# host_connector.net
KiCad netlist of a schematic drawn in Altium Designer
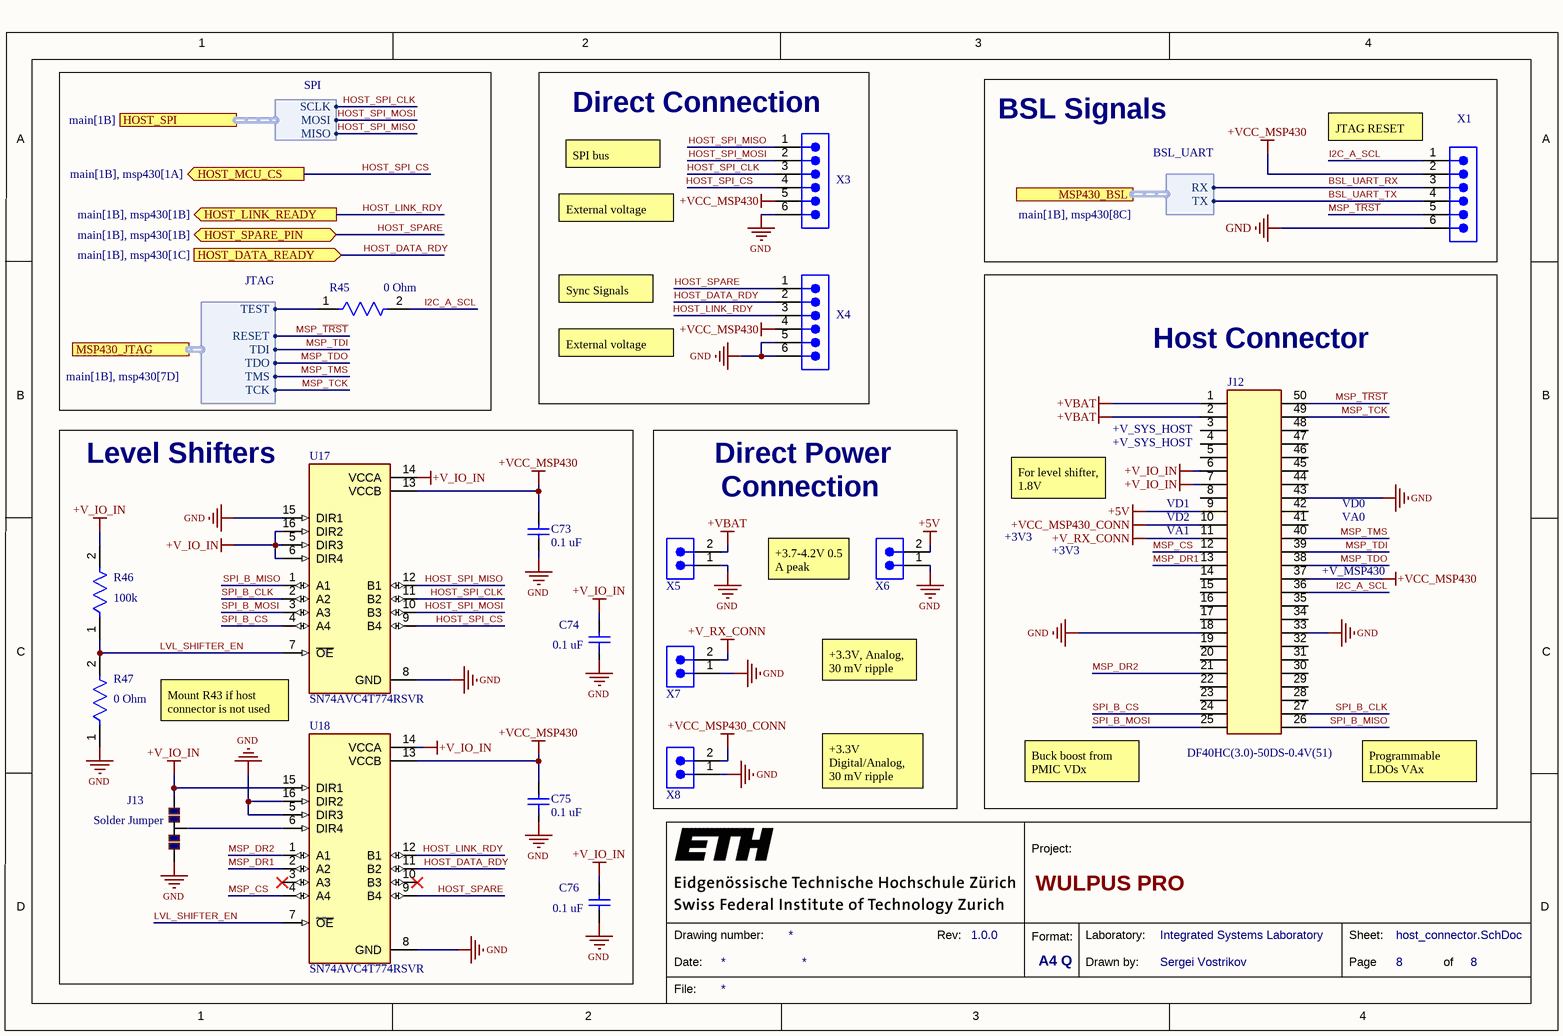
[diagram p0: host_connector.SchDoc]

(export (version "E")
  (design (tool "Eeschema 10.0.6"))
  (components
    (comp (ref "C73")
      (value "0.1 uF")
      (footprint "CAPC1005X55X30LL05T10")
      (description "C0402C104K4RACTU")
      (fields (field (name "MANUFACTURER") "Kemet"))
      (libsource (lib "Altium Content Vault") (part "CAP"))
    )
    (comp (ref "C74")
      (value "0.1 uF")
      (footprint "CAPC1005X55X30LL05T10")
      (description "C0402C104K4RACTU")
      (fields (field (name "MANUFACTURER") "Kemet"))
      (libsource (lib "Altium Content Vault") (part "CAP"))
    )
    (comp (ref "C75")
      (value "0.1 uF")
      (footprint "CAPC1005X55X30LL05T10")
      (description "C0402C104K4RACTU")
      (fields (field (name "MANUFACTURER") "Kemet"))
      (libsource (lib "Altium Content Vault") (part "CAP"))
    )
    (comp (ref "C76")
      (value "0.1 uF")
      (footprint "CAPC1005X55X30LL05T10")
      (description "C0402C104K4RACTU")
      (fields (field (name "MANUFACTURER") "Kemet"))
      (libsource (lib "Altium Content Vault") (part "CAP"))
    )
    (comp (ref "J12")
      (value "DF40HC(3.0)-50DS-0.4V(51)")
      (footprint "DF40HC3050DS04V51")
      (description "50 Position 0.4mm Pitch Dual Row Vertical Surface Mount (SMT) Pin Socket, 3.0mm Stacking Height")
      (fields (field (name "COPYRIGHT") "Copyright (C) 2023 Ultra Librarian. All rights reserved."))
      (libsource (lib "host_connectors") (part "DF40HC(3.0)-50DS-0.4V(51)"))
    )
    (comp (ref "J13")
      (value "Solder Jumper")
      (footprint "Jumper 3 pins")
      (description "Solder Jumper 3 Pads")
      (libsource (lib "ETHZ Vault") (part "Solder Jumper 3-pads"))
    )
    (comp (ref "R45")
      (value "0 Ohm")
      (footprint "FP-CRCW0402-e3-IPC_C")
      (description "CRCW04020000Z0ED")
      (fields (field (name "TOLERANCE") "5%"))
      (libsource (lib "Altium Content Vault") (part "1029c3af85768c4190bb7ad29bc67b5"))
    )
    (comp (ref "R46")
      (value "100k")
      (footprint "FP-ERJ2RK-IPC_C")
      (description "ERJ-2RKF1003X")
      (fields (field (name "TOLERANCE") "1%"))
      (libsource (lib "Altium Content Vault") (part "1029c3af85768c4190bb7ad29bc67b5"))
    )
    (comp (ref "R47")
      (value "0 Ohm")
      (footprint "FP-CRCW0402-e3-IPC_C")
      (description "CRCW04020000Z0ED")
      (fields (field (name "TOLERANCE") "5%"))
      (libsource (lib "Altium Content Vault") (part "1029c3af85768c4190bb7ad29bc67b5"))
    )
    (comp (ref "U17")
      (value "SN74AVC4T774RSVR")
      (footprint "QFN40P260X180X55-16N")
      (description "Voltage Level Translator Bidirectional 1 Circuit 4 Channel 380Mbps 16-UQFN _2.6x1.8_")
      (fields (field (name "DIGI-KEY_PART_NUMBER") "296-24741-1-ND") (field (name "MF") "Texas Instruments"))
      (libsource (lib "SN74AVC4T774RSVR") (part "SN74AVC4T774RSVR"))
    )
    (comp (ref "U18")
      (value "SN74AVC4T774RSVR")
      (footprint "QFN40P260X180X55-16N")
      (description "Voltage Level Translator Bidirectional 1 Circuit 4 Channel 380Mbps 16-UQFN _2.6x1.8_")
      (fields (field (name "DIGI-KEY_PART_NUMBER") "296-24741-1-ND") (field (name "MF") "Texas Instruments"))
      (libsource (lib "SN74AVC4T774RSVR") (part "SN74AVC4T774RSVR"))
    )
    (comp (ref "X1")
      (value "68000-106HLF")
      (footprint "68000-106HLF")
      (description "6 Positions Header, Unshrouded Connector 0.100\" (2.54mm) Through Hole Gold or Gold, GXT™")
      (libsource (lib "ETHZ Vault") (part "CON-1x6-Male"))
    )
    (comp (ref "X3")
      (value "68000-106HLF")
      (footprint "68000-106HLF")
      (description "6 Positions Header, Unshrouded Connector 0.100\" (2.54mm) Through Hole Gold or Gold, GXT™")
      (libsource (lib "ETHZ Vault") (part "CON-1x6-Male"))
    )
    (comp (ref "X4")
      (value "68000-106HLF")
      (footprint "68000-106HLF")
      (description "6 Positions Header, Unshrouded Connector 0.100\" (2.54mm) Through Hole Gold or Gold, GXT™")
      (libsource (lib "ETHZ Vault") (part "CON-1x6-Male"))
    )
    (comp (ref "X5")
      (value "68000-102HLF")
      (footprint "68000-102HLF")
      (description "2 Positions Header, Unshrouded Connector 0.100\" (2.54mm) Through Hole Gold or Gold, GXT™")
      (fields (field (name "MANUFACTURER") "Amphenol FCI"))
      (libsource (lib "ETHZ Vault") (part "CON-1x2-Male"))
    )
    (comp (ref "X6")
      (value "68000-102HLF")
      (footprint "68000-102HLF")
      (description "2 Positions Header, Unshrouded Connector 0.100\" (2.54mm) Through Hole Gold or Gold, GXT™")
      (fields (field (name "MANUFACTURER") "Amphenol FCI"))
      (libsource (lib "ETHZ Vault") (part "CON-1x2-Male"))
    )
    (comp (ref "X7")
      (value "68000-102HLF")
      (footprint "68000-102HLF")
      (description "2 Positions Header, Unshrouded Connector 0.100\" (2.54mm) Through Hole Gold or Gold, GXT™")
      (fields (field (name "MANUFACTURER") "Amphenol FCI"))
      (libsource (lib "ETHZ Vault") (part "CON-1x2-Male"))
    )
    (comp (ref "X8")
      (value "68000-102HLF")
      (footprint "68000-102HLF")
      (description "2 Positions Header, Unshrouded Connector 0.100\" (2.54mm) Through Hole Gold or Gold, GXT™")
      (fields (field (name "MANUFACTURER") "Amphenol FCI"))
      (libsource (lib "ETHZ Vault") (part "CON-1x2-Male"))
    )
  )
  (nets
    (net (code "4") (name "+5V") (class "Default")
      (node (ref "J12") (pin "9") (pintype "passive"))
      (node (ref "X6") (pin "2") (pinfunction "2_2") (pintype "passive"))
    )
    (net (code "5") (name "+VBAT") (class "Default")
      (node (ref "J12") (pin "1") (pintype "passive"))
      (node (ref "J12") (pin "2") (pintype "passive"))
      (node (ref "X5") (pin "2") (pinfunction "2_2") (pintype "passive"))
    )
    (net (code "6") (name "+VCC_MSP430") (class "Default")
      (node (ref "C73") (pin "1") (pinfunction "1_1") (pintype "passive"))
      (node (ref "C75") (pin "1") (pinfunction "1_1") (pintype "passive"))
      (node (ref "J12") (pin "37") (pintype "passive"))
      (node (ref "U17") (pin "13") (pinfunction "VCCB_13") (pintype "power_in"))
      (node (ref "U18") (pin "13") (pinfunction "VCCB_13") (pintype "power_in"))
      (node (ref "X1") (pin "2") (pinfunction "2_2") (pintype "passive"))
      (node (ref "X3") (pin "5") (pinfunction "5_5") (pintype "passive"))
      (node (ref "X4") (pin "4") (pinfunction "4_4") (pintype "passive"))
    )
    (net (code "7") (name "+VCC_MSP430_CONN") (class "Default")
      (node (ref "J12") (pin "10") (pintype "passive"))
      (node (ref "X8") (pin "2") (pinfunction "2_2") (pintype "passive"))
    )
    (net (code "8") (name "+V_IO_IN") (class "Default")
      (node (ref "C74") (pin "1") (pinfunction "1_1") (pintype "passive"))
      (node (ref "C76") (pin "1") (pinfunction "1_1") (pintype "passive"))
      (node (ref "J12") (pin "6") (pintype "passive"))
      (node (ref "J12") (pin "7") (pintype "passive"))
      (node (ref "J13") (pin "3") (pinfunction "3_3") (pintype "passive"))
      (node (ref "R46") (pin "2") (pinfunction "2_2") (pintype "passive"))
      (node (ref "U17") (pin "14") (pinfunction "VCCA_14") (pintype "power_in"))
      (node (ref "U17") (pin "16") (pinfunction "DIR2_16") (pintype "input"))
      (node (ref "U17") (pin "5") (pinfunction "DIR3_5") (pintype "input"))
      (node (ref "U17") (pin "6") (pinfunction "DIR4_6") (pintype "input"))
      (node (ref "U18") (pin "14") (pinfunction "VCCA_14") (pintype "power_in"))
      (node (ref "U18") (pin "15") (pinfunction "DIR1_15") (pintype "input"))
    )
    (net (code "9") (name "+V_RX_CONN") (class "Default")
      (node (ref "J12") (pin "11") (pintype "passive"))
      (node (ref "X7") (pin "2") (pinfunction "2_2") (pintype "passive"))
    )
    (net (code "10") (name "/BSL_UART_RX") (class "Default")
      (node (ref "X1") (pin "3") (pinfunction "3_3") (pintype "passive"))
    )
    (net (code "11") (name "/BSL_UART_TX") (class "Default")
      (node (ref "X1") (pin "4") (pinfunction "4_4") (pintype "passive"))
    )
    (net (code "12") (name "/HOST_DATA_RDY") (class "Default")
      (node (ref "U18") (pin "11") (pinfunction "B2_11") (pintype "bidirectional"))
      (node (ref "X4") (pin "2") (pinfunction "2_2") (pintype "passive"))
    )
    (net (code "13") (name "/HOST_LINK_RDY") (class "Default")
      (node (ref "U18") (pin "12") (pinfunction "B1_12") (pintype "bidirectional"))
      (node (ref "X4") (pin "3") (pinfunction "3_3") (pintype "passive"))
    )
    (net (code "14") (name "/HOST_SPARE") (class "Default")
      (node (ref "U18") (pin "9") (pinfunction "B4_9") (pintype "bidirectional"))
      (node (ref "X4") (pin "1") (pinfunction "1_1") (pintype "passive"))
    )
    (net (code "15") (name "/HOST_SPI_CLK") (class "Default")
      (node (ref "U17") (pin "11") (pinfunction "B2_11") (pintype "bidirectional"))
      (node (ref "X3") (pin "3") (pinfunction "3_3") (pintype "passive"))
    )
    (net (code "16") (name "/HOST_SPI_CS") (class "Default")
      (node (ref "U17") (pin "9") (pinfunction "B4_9") (pintype "bidirectional"))
      (node (ref "X3") (pin "4") (pinfunction "4_4") (pintype "passive"))
    )
    (net (code "17") (name "/HOST_SPI_MISO") (class "Default")
      (node (ref "U17") (pin "12") (pinfunction "B1_12") (pintype "bidirectional"))
      (node (ref "X3") (pin "1") (pinfunction "1_1") (pintype "passive"))
    )
    (net (code "18") (name "/HOST_SPI_MOSI") (class "Default")
      (node (ref "U17") (pin "10") (pinfunction "B3_10") (pintype "bidirectional"))
      (node (ref "X3") (pin "2") (pinfunction "2_2") (pintype "passive"))
    )
    (net (code "19") (name "/I2C_A_SCL") (class "Default")
      (node (ref "J12") (pin "36") (pintype "passive"))
      (node (ref "R45") (pin "2") (pinfunction "2_2") (pintype "passive"))
      (node (ref "X1") (pin "1") (pinfunction "1_1") (pintype "passive"))
    )
    (net (code "20") (name "/LVL_SHIFTER_EN") (class "Default")
      (node (ref "R46") (pin "1") (pinfunction "1_1") (pintype "passive"))
      (node (ref "R47") (pin "2") (pinfunction "2_2") (pintype "passive"))
      (node (ref "U17") (pin "7") (pinfunction "~{OE}_7") (pintype "input"))
      (node (ref "U18") (pin "7") (pinfunction "~{OE}_7") (pintype "input"))
    )
    (net (code "21") (name "/MSP_CS") (class "Default")
      (node (ref "J12") (pin "12") (pintype "passive"))
      (node (ref "U18") (pin "4") (pinfunction "A4_4") (pintype "bidirectional"))
    )
    (net (code "22") (name "/MSP_DR1") (class "Default")
      (node (ref "J12") (pin "13") (pintype "passive"))
      (node (ref "U18") (pin "2") (pinfunction "A2_2") (pintype "bidirectional"))
    )
    (net (code "23") (name "/MSP_DR2") (class "Default")
      (node (ref "J12") (pin "21") (pintype "passive"))
      (node (ref "U18") (pin "1") (pinfunction "A1_1") (pintype "bidirectional"))
    )
    (net (code "24") (name "/MSP_TCK") (class "Default") (node (ref "J12") (pin "49") (pintype "passive")))
    (net (code "25") (name "/MSP_TDI") (class "Default") (node (ref "J12") (pin "39") (pintype "passive")))
    (net (code "26") (name "/MSP_TDO") (class "Default") (node (ref "J12") (pin "38") (pintype "passive")))
    (net (code "27") (name "/MSP_TMS") (class "Default") (node (ref "J12") (pin "40") (pintype "passive")))
    (net (code "28") (name "/MSP_~{TRST}") (class "Default")
      (node (ref "J12") (pin "50") (pintype "passive"))
      (node (ref "X1") (pin "5") (pinfunction "5_5") (pintype "passive"))
    )
    (net (code "29") (name "/SPI_B_CLK") (class "Default")
      (node (ref "J12") (pin "27") (pintype "passive"))
      (node (ref "U17") (pin "2") (pinfunction "A2_2") (pintype "bidirectional"))
    )
    (net (code "30") (name "/SPI_B_CS") (class "Default")
      (node (ref "J12") (pin "24") (pintype "passive"))
      (node (ref "U17") (pin "4") (pinfunction "A4_4") (pintype "bidirectional"))
    )
    (net (code "31") (name "/SPI_B_MISO") (class "Default")
      (node (ref "J12") (pin "26") (pintype "passive"))
      (node (ref "U17") (pin "1") (pinfunction "A1_1") (pintype "bidirectional"))
    )
    (net (code "32") (name "/SPI_B_MOSI") (class "Default")
      (node (ref "J12") (pin "25") (pintype "passive"))
      (node (ref "U17") (pin "3") (pinfunction "A3_3") (pintype "bidirectional"))
    )
    (net (code "33") (name "/TEST") (class "Default")
      (node (ref "R45") (pin "1") (pinfunction "1_1") (pintype "passive"))
    )
    (net (code "37") (name "GND") (class "Default")
      (node (ref "C73") (pin "2") (pinfunction "2_2") (pintype "passive"))
      (node (ref "C74") (pin "2") (pinfunction "2_2") (pintype "passive"))
      (node (ref "C75") (pin "2") (pinfunction "2_2") (pintype "passive"))
      (node (ref "C76") (pin "2") (pinfunction "2_2") (pintype "passive"))
      (node (ref "J12") (pin "18") (pintype "passive"))
      (node (ref "J12") (pin "33") (pintype "passive"))
      (node (ref "J12") (pin "43") (pintype "passive"))
      (node (ref "J13") (pin "1") (pinfunction "1_1") (pintype "passive"))
      (node (ref "R47") (pin "1") (pinfunction "1_1") (pintype "passive"))
      (node (ref "U17") (pin "15") (pinfunction "DIR1_15") (pintype "input"))
      (node (ref "U17") (pin "8") (pinfunction "GND_8") (pintype "power_in"))
      (node (ref "U18") (pin "16") (pinfunction "DIR2_16") (pintype "input"))
      (node (ref "U18") (pin "5") (pinfunction "DIR3_5") (pintype "input"))
      (node (ref "U18") (pin "8") (pinfunction "GND_8") (pintype "power_in"))
      (node (ref "X1") (pin "6") (pinfunction "6_6") (pintype "passive"))
      (node (ref "X3") (pin "6") (pinfunction "6_6") (pintype "passive"))
      (node (ref "X4") (pin "5") (pinfunction "5_5") (pintype "passive"))
      (node (ref "X4") (pin "6") (pinfunction "6_6") (pintype "passive"))
      (node (ref "X5") (pin "1") (pinfunction "1_1") (pintype "passive"))
      (node (ref "X6") (pin "1") (pinfunction "1_1") (pintype "passive"))
      (node (ref "X7") (pin "1") (pinfunction "1_1") (pintype "passive"))
      (node (ref "X8") (pin "1") (pinfunction "1_1") (pintype "passive"))
    )
    (net (code "38") (name "Net-(U18-DIR4)") (class "Default")
      (node (ref "J13") (pin "2") (pinfunction "2_2") (pintype "passive"))
      (node (ref "U18") (pin "6") (pinfunction "DIR4_6") (pintype "input"))
    )
    (net (code "39") (name "unconnected-(J12-Pad3)") (class "Default")
      (node (ref "J12") (pin "3") (pintype "passive"))
    )
    (net (code "40") (name "unconnected-(J12-Pad4)") (class "Default")
      (node (ref "J12") (pin "4") (pintype "passive"))
    )
    (net (code "41") (name "unconnected-(J12-Pad5)") (class "Default")
      (node (ref "J12") (pin "5") (pintype "passive"))
    )
    (net (code "42") (name "unconnected-(J12-Pad8)") (class "Default")
      (node (ref "J12") (pin "8") (pintype "passive"))
    )
    (net (code "43") (name "unconnected-(J12-Pad14)") (class "Default")
      (node (ref "J12") (pin "14") (pintype "passive"))
    )
    (net (code "44") (name "unconnected-(J12-Pad15)") (class "Default")
      (node (ref "J12") (pin "15") (pintype "passive"))
    )
    (net (code "45") (name "unconnected-(J12-Pad16)") (class "Default")
      (node (ref "J12") (pin "16") (pintype "passive"))
    )
    (net (code "46") (name "unconnected-(J12-Pad17)") (class "Default")
      (node (ref "J12") (pin "17") (pintype "passive"))
    )
    (net (code "47") (name "unconnected-(J12-Pad19)") (class "Default")
      (node (ref "J12") (pin "19") (pintype "passive"))
    )
    (net (code "48") (name "unconnected-(J12-Pad20)") (class "Default")
      (node (ref "J12") (pin "20") (pintype "passive"))
    )
    (net (code "49") (name "unconnected-(J12-Pad22)") (class "Default")
      (node (ref "J12") (pin "22") (pintype "passive"))
    )
    (net (code "50") (name "unconnected-(J12-Pad23)") (class "Default")
      (node (ref "J12") (pin "23") (pintype "passive"))
    )
    (net (code "51") (name "unconnected-(J12-Pad28)") (class "Default")
      (node (ref "J12") (pin "28") (pintype "passive"))
    )
    (net (code "52") (name "unconnected-(J12-Pad29)") (class "Default")
      (node (ref "J12") (pin "29") (pintype "passive"))
    )
    (net (code "53") (name "unconnected-(J12-Pad30)") (class "Default")
      (node (ref "J12") (pin "30") (pintype "passive"))
    )
    (net (code "54") (name "unconnected-(J12-Pad31)") (class "Default")
      (node (ref "J12") (pin "31") (pintype "passive"))
    )
    (net (code "55") (name "unconnected-(J12-Pad32)") (class "Default")
      (node (ref "J12") (pin "32") (pintype "passive"))
    )
    (net (code "56") (name "unconnected-(J12-Pad34)") (class "Default")
      (node (ref "J12") (pin "34") (pintype "passive"))
    )
    (net (code "57") (name "unconnected-(J12-Pad35)") (class "Default")
      (node (ref "J12") (pin "35") (pintype "passive"))
    )
    (net (code "58") (name "unconnected-(J12-Pad41)") (class "Default")
      (node (ref "J12") (pin "41") (pintype "passive"))
    )
    (net (code "59") (name "unconnected-(J12-Pad42)") (class "Default")
      (node (ref "J12") (pin "42") (pintype "passive"))
    )
    (net (code "60") (name "unconnected-(J12-Pad44)") (class "Default")
      (node (ref "J12") (pin "44") (pintype "passive"))
    )
    (net (code "61") (name "unconnected-(J12-Pad45)") (class "Default")
      (node (ref "J12") (pin "45") (pintype "passive"))
    )
    (net (code "62") (name "unconnected-(J12-Pad46)") (class "Default")
      (node (ref "J12") (pin "46") (pintype "passive"))
    )
    (net (code "63") (name "unconnected-(J12-Pad47)") (class "Default")
      (node (ref "J12") (pin "47") (pintype "passive"))
    )
    (net (code "64") (name "unconnected-(J12-Pad48)") (class "Default")
      (node (ref "J12") (pin "48") (pintype "passive"))
    )
    (net (code "65") (name "unconnected-(U18-A3-Pad3)") (class "Default")
      (node (ref "U18") (pin "3") (pinfunction "A3_3") (pintype "bidirectional+no_connect"))
    )
    (net (code "66") (name "unconnected-(U18-B3-Pad10)") (class "Default")
      (node (ref "U18") (pin "10") (pinfunction "B3_10") (pintype "bidirectional+no_connect"))
    )
  )
)
